# Contactless.net
KiCad netlist of a schematic drawn in EAGLE
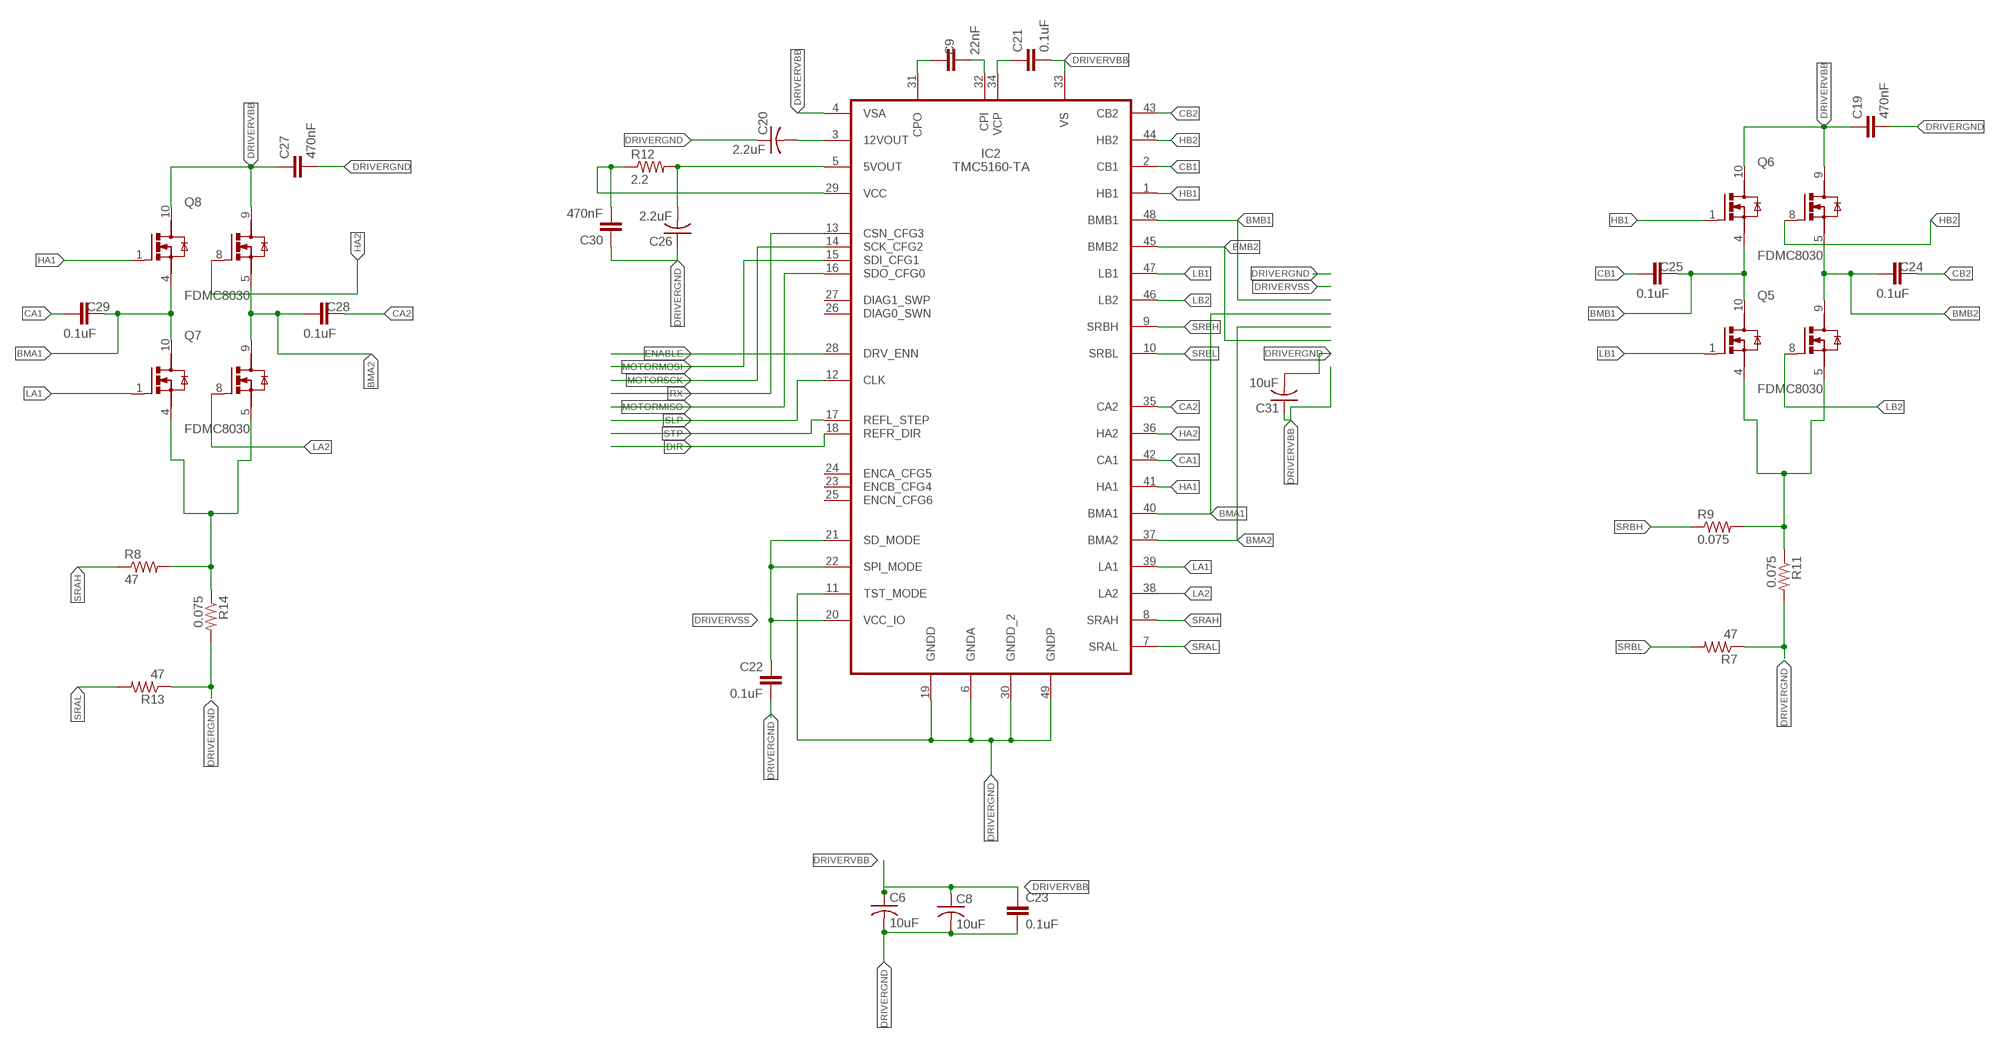
[diagram p0: schematic, sheet 1]

(export (version "E")
  (design (tool "Eeschema 10.0.6"))
  (components
    (comp (ref "C6")
      (value "10uF")
      (footprint "eagle-import:C0805")
      (libsource (lib "eagle-import") (part "C-USC0805"))
    )
    (comp (ref "C8")
      (value "10uF")
      (footprint "eagle-import:C0805")
      (libsource (lib "eagle-import") (part "C-USC0805"))
    )
    (comp (ref "C9")
      (value "22nF")
      (footprint "eagle-import:0603")
      (libsource (lib "eagle-import") (part "22NF/22,000PF-0603-50V-10%"))
    )
    (comp (ref "C19")
      (value "470nF")
      (footprint "eagle-import:0402")
      (libsource (lib "eagle-import") (part "470NF-0402-16V-10%"))
    )
    (comp (ref "C20")
      (value "2.2uF")
      (footprint "eagle-import:C0402")
      (libsource (lib "eagle-import") (part "C-USC0402"))
    )
    (comp (ref "C21")
      (value "0.1uF")
      (footprint "eagle-import:0402")
      (libsource (lib "eagle-import") (part "0.1UF-0402-16V-10%"))
    )
    (comp (ref "C22")
      (value "0.1uF")
      (footprint "eagle-import:0402")
      (libsource (lib "eagle-import") (part "0.1UF-0402-16V-10%"))
    )
    (comp (ref "C23")
      (value "0.1uF")
      (footprint "eagle-import:0402")
      (libsource (lib "eagle-import") (part "0.1UF-0402-16V-10%"))
    )
    (comp (ref "C24")
      (value "0.1uF")
      (footprint "eagle-import:0402")
      (libsource (lib "eagle-import") (part "0.1UF-0402-16V-10%"))
    )
    (comp (ref "C25")
      (value "0.1uF")
      (footprint "eagle-import:0402")
      (libsource (lib "eagle-import") (part "0.1UF-0402-16V-10%"))
    )
    (comp (ref "C26")
      (value "2.2uF")
      (footprint "eagle-import:C0402")
      (libsource (lib "eagle-import") (part "C-USC0402"))
    )
    (comp (ref "C27")
      (value "470nF")
      (footprint "eagle-import:0402")
      (libsource (lib "eagle-import") (part "470NF-0402-16V-10%"))
    )
    (comp (ref "C28")
      (value "0.1uF")
      (footprint "eagle-import:0402")
      (libsource (lib "eagle-import") (part "0.1UF-0402-16V-10%"))
    )
    (comp (ref "C29")
      (value "0.1uF")
      (footprint "eagle-import:0402")
      (libsource (lib "eagle-import") (part "0.1UF-0402-16V-10%"))
    )
    (comp (ref "C30")
      (value "470nF")
      (footprint "eagle-import:0402")
      (libsource (lib "eagle-import") (part "470NF-0402-16V-10%"))
    )
    (comp (ref "C31")
      (value "10uF")
      (footprint "eagle-import:C0805")
      (libsource (lib "eagle-import") (part "C-USC0805"))
    )
    (comp (ref "IC2")
      (value "TMC5160-TA")
      (footprint "eagle-import:TQFP48-EP")
      (fields (field (name "MF") "Trinamic Motion"))
      (libsource (lib "eagle-import") (part "TMC5160-TA"))
    )
    (comp (ref "Q5")
      (value "FDMC8030")
      (footprint "eagle-import:TRANS_FDMC8030")
      (fields (field (name "MF") "ON Semiconductor"))
      (libsource (lib "eagle-import") (part "FDMC8030"))
    )
    (comp (ref "Q6")
      (value "FDMC8030")
      (footprint "eagle-import:TRANS_FDMC8030")
      (fields (field (name "MF") "ON Semiconductor"))
      (libsource (lib "eagle-import") (part "FDMC8030"))
    )
    (comp (ref "Q7")
      (value "FDMC8030")
      (footprint "eagle-import:TRANS_FDMC8030")
      (fields (field (name "MF") "ON Semiconductor"))
      (libsource (lib "eagle-import") (part "FDMC8030"))
    )
    (comp (ref "Q8")
      (value "FDMC8030")
      (footprint "eagle-import:TRANS_FDMC8030")
      (fields (field (name "MF") "ON Semiconductor"))
      (libsource (lib "eagle-import") (part "FDMC8030"))
    )
    (comp (ref "R7")
      (value "47")
      (footprint "eagle-import:R0402")
      (libsource (lib "eagle-import") (part "R-US_R0402"))
    )
    (comp (ref "R8")
      (value "47")
      (footprint "eagle-import:R0402")
      (libsource (lib "eagle-import") (part "R-US_R0402"))
    )
    (comp (ref "R9")
      (value "0.075")
      (footprint "eagle-import:R1206")
      (libsource (lib "eagle-import") (part "R-US_R1206"))
    )
    (comp (ref "R11")
      (value "0.075")
      (footprint "eagle-import:R1206")
      (libsource (lib "eagle-import") (part "R-US_R1206"))
    )
    (comp (ref "R12")
      (value "2.2")
      (footprint "eagle-import:R0402")
      (libsource (lib "eagle-import") (part "R-US_R0402"))
    )
    (comp (ref "R13")
      (value "47")
      (footprint "eagle-import:R0402")
      (libsource (lib "eagle-import") (part "R-US_R0402"))
    )
    (comp (ref "R14")
      (value "0.075")
      (footprint "eagle-import:R1206")
      (libsource (lib "eagle-import") (part "R-US_R1206"))
    )
  )
  (nets
    (net (code "1") (name "BMA1") (class "Default")
      (node (ref "C29") (pin "2") (pinfunction "2_2") (pintype "passive"))
      (node (ref "IC2") (pin "40") (pinfunction "BMA1_40") (pintype "input"))
      (node (ref "Q7") (pin "10") (pinfunction "D1_10") (pintype "passive"))
      (node (ref "Q8") (pin "4") (pinfunction "S1_4") (pintype "passive"))
    )
    (net (code "2") (name "BMA2") (class "Default")
      (node (ref "C28") (pin "1") (pinfunction "1_1") (pintype "passive"))
      (node (ref "IC2") (pin "37") (pinfunction "BMA2_37") (pintype "input"))
      (node (ref "Q7") (pin "9") (pinfunction "D2_9") (pintype "passive"))
      (node (ref "Q8") (pin "5") (pinfunction "S2_5") (pintype "passive"))
    )
    (net (code "3") (name "BMB1") (class "Default")
      (node (ref "C25") (pin "2") (pinfunction "2_2") (pintype "passive"))
      (node (ref "IC2") (pin "48") (pinfunction "BMB1_48") (pintype "input"))
      (node (ref "Q5") (pin "10") (pinfunction "D1_10") (pintype "passive"))
      (node (ref "Q6") (pin "4") (pinfunction "S1_4") (pintype "passive"))
    )
    (net (code "4") (name "BMB2") (class "Default")
      (node (ref "C24") (pin "1") (pinfunction "1_1") (pintype "passive"))
      (node (ref "IC2") (pin "45") (pinfunction "BMB2_45") (pintype "input"))
      (node (ref "Q5") (pin "9") (pinfunction "D2_9") (pintype "passive"))
      (node (ref "Q6") (pin "5") (pinfunction "S2_5") (pintype "passive"))
    )
    (net (code "5") (name "CA1") (class "Default")
      (node (ref "C29") (pin "1") (pinfunction "1_1") (pintype "passive"))
      (node (ref "IC2") (pin "42") (pinfunction "CA1_42") (pintype "input"))
    )
    (net (code "6") (name "CA2") (class "Default")
      (node (ref "C28") (pin "2") (pinfunction "2_2") (pintype "passive"))
      (node (ref "IC2") (pin "35") (pinfunction "CA2_35") (pintype "input"))
    )
    (net (code "7") (name "CB1") (class "Default")
      (node (ref "C25") (pin "1") (pinfunction "1_1") (pintype "passive"))
      (node (ref "IC2") (pin "2") (pinfunction "CB1_2") (pintype "input"))
    )
    (net (code "8") (name "CB2") (class "Default")
      (node (ref "C24") (pin "2") (pinfunction "2_2") (pintype "passive"))
      (node (ref "IC2") (pin "43") (pinfunction "CB2_43") (pintype "input"))
    )
    (net (code "9") (name "DIR") (class "Default")
      (node (ref "IC2") (pin "18") (pinfunction "REFR_DIR_18") (pintype "input"))
    )
    (net (code "10") (name "DRIVERGND") (class "Default")
      (node (ref "C19") (pin "2") (pinfunction "2_2") (pintype "passive"))
      (node (ref "C20") (pin "1") (pinfunction "1_1") (pintype "passive"))
      (node (ref "C22") (pin "2") (pinfunction "2_2") (pintype "passive"))
      (node (ref "C23") (pin "2") (pinfunction "2_2") (pintype "passive"))
      (node (ref "C26") (pin "1") (pinfunction "1_1") (pintype "passive"))
      (node (ref "C27") (pin "2") (pinfunction "2_2") (pintype "passive"))
      (node (ref "C30") (pin "1") (pinfunction "1_1") (pintype "passive"))
      (node (ref "C31") (pin "2") (pinfunction "2_2") (pintype "passive"))
      (node (ref "C6") (pin "2") (pinfunction "2_2") (pintype "passive"))
      (node (ref "C8") (pin "2") (pinfunction "2_2") (pintype "passive"))
      (node (ref "IC2") (pin "11") (pinfunction "TST_MODE_11") (pintype "input"))
      (node (ref "IC2") (pin "19") (pinfunction "GNDD_19") (pintype "power_in"))
      (node (ref "IC2") (pin "30") (pinfunction "GNDD_2_30") (pintype "power_in"))
      (node (ref "IC2") (pin "49") (pinfunction "GNDP_49") (pintype "power_in"))
      (node (ref "IC2") (pin "6") (pinfunction "GNDA_6") (pintype "power_in"))
      (node (ref "R11") (pin "2") (pinfunction "2_2") (pintype "passive"))
      (node (ref "R13") (pin "1") (pinfunction "1_1") (pintype "passive"))
      (node (ref "R14") (pin "2") (pinfunction "2_2") (pintype "passive"))
      (node (ref "R7") (pin "1") (pinfunction "1_1") (pintype "passive"))
    )
    (net (code "11") (name "DRIVERVBB") (class "Default")
      (node (ref "C19") (pin "1") (pinfunction "1_1") (pintype "passive"))
      (node (ref "C21") (pin "2") (pinfunction "2_2") (pintype "passive"))
      (node (ref "C23") (pin "1") (pinfunction "1_1") (pintype "passive"))
      (node (ref "C27") (pin "1") (pinfunction "1_1") (pintype "passive"))
      (node (ref "C31") (pin "1") (pinfunction "1_1") (pintype "passive"))
      (node (ref "C6") (pin "1") (pinfunction "1_1") (pintype "passive"))
      (node (ref "C8") (pin "1") (pinfunction "1_1") (pintype "passive"))
      (node (ref "IC2") (pin "33") (pinfunction "VS_33") (pintype "power_in"))
      (node (ref "IC2") (pin "4") (pinfunction "VSA_4") (pintype "power_in"))
      (node (ref "Q6") (pin "10") (pinfunction "D1_10") (pintype "passive"))
      (node (ref "Q6") (pin "9") (pinfunction "D2_9") (pintype "passive"))
      (node (ref "Q8") (pin "10") (pinfunction "D1_10") (pintype "passive"))
      (node (ref "Q8") (pin "9") (pinfunction "D2_9") (pintype "passive"))
    )
    (net (code "12") (name "DRIVERVSS") (class "Default")
      (node (ref "C22") (pin "1") (pinfunction "1_1") (pintype "passive"))
      (node (ref "IC2") (pin "20") (pinfunction "VCC_IO_20") (pintype "power_in"))
      (node (ref "IC2") (pin "21") (pinfunction "SD_MODE_21") (pintype "input"))
      (node (ref "IC2") (pin "22") (pinfunction "SPI_MODE_22") (pintype "input"))
    )
    (net (code "13") (name "ENABLE") (class "Default")
      (node (ref "IC2") (pin "28") (pinfunction "DRV_ENN_28") (pintype "input"))
    )
    (net (code "14") (name "HA1") (class "Default")
      (node (ref "IC2") (pin "41") (pinfunction "HA1_41") (pintype "output"))
      (node (ref "Q8") (pin "1") (pinfunction "G1_1") (pintype "passive"))
    )
    (net (code "15") (name "HA2") (class "Default")
      (node (ref "IC2") (pin "36") (pinfunction "HA2_36") (pintype "output"))
      (node (ref "Q8") (pin "8") (pinfunction "G2_8") (pintype "passive"))
    )
    (net (code "16") (name "HB1") (class "Default")
      (node (ref "IC2") (pin "1") (pinfunction "HB1_1") (pintype "output"))
      (node (ref "Q6") (pin "1") (pinfunction "G1_1") (pintype "passive"))
    )
    (net (code "17") (name "HB2") (class "Default")
      (node (ref "IC2") (pin "44") (pinfunction "HB2_44") (pintype "output"))
      (node (ref "Q6") (pin "8") (pinfunction "G2_8") (pintype "passive"))
    )
    (net (code "18") (name "LA1") (class "Default")
      (node (ref "IC2") (pin "39") (pinfunction "LA1_39") (pintype "output"))
      (node (ref "Q7") (pin "1") (pinfunction "G1_1") (pintype "passive"))
    )
    (net (code "19") (name "LA2") (class "Default")
      (node (ref "IC2") (pin "38") (pinfunction "LA2_38") (pintype "output"))
      (node (ref "Q7") (pin "8") (pinfunction "G2_8") (pintype "passive"))
    )
    (net (code "20") (name "LB1") (class "Default")
      (node (ref "IC2") (pin "47") (pinfunction "LB1_47") (pintype "output"))
      (node (ref "Q5") (pin "1") (pinfunction "G1_1") (pintype "passive"))
    )
    (net (code "21") (name "LB2") (class "Default")
      (node (ref "IC2") (pin "46") (pinfunction "LB2_46") (pintype "output"))
      (node (ref "Q5") (pin "8") (pinfunction "G2_8") (pintype "passive"))
    )
    (net (code "22") (name "MOTORMISO") (class "Default")
      (node (ref "IC2") (pin "16") (pinfunction "SDO_CFG0_16") (pintype "output"))
    )
    (net (code "23") (name "MOTORMOSI") (class "Default")
      (node (ref "IC2") (pin "15") (pinfunction "SDI_CFG1_15") (pintype "input"))
    )
    (net (code "24") (name "MOTORSCK") (class "Default")
      (node (ref "IC2") (pin "14") (pinfunction "SCK_CFG2_14") (pintype "input"))
    )
    (net (code "25") (name "Net-(IC2-5VOUT)") (class "Default")
      (node (ref "C26") (pin "2") (pinfunction "2_2") (pintype "passive"))
      (node (ref "IC2") (pin "5") (pinfunction "5VOUT_5") (pintype "bidirectional"))
      (node (ref "R12") (pin "2") (pinfunction "2_2") (pintype "passive"))
    )
    (net (code "26") (name "Net-(IC2-12VOUT)") (class "Default")
      (node (ref "C20") (pin "2") (pinfunction "2_2") (pintype "passive"))
      (node (ref "IC2") (pin "3") (pinfunction "12VOUT_3") (pintype "bidirectional"))
    )
    (net (code "27") (name "Net-(IC2-CPI)") (class "Default")
      (node (ref "C9") (pin "2") (pinfunction "2_2") (pintype "passive"))
      (node (ref "IC2") (pin "32") (pinfunction "CPI_32") (pintype "input"))
    )
    (net (code "28") (name "Net-(IC2-CPO)") (class "Default")
      (node (ref "C9") (pin "1") (pinfunction "1_1") (pintype "passive"))
      (node (ref "IC2") (pin "31") (pinfunction "CPO_31") (pintype "input"))
    )
    (net (code "29") (name "Net-(IC2-VCC)") (class "Default")
      (node (ref "C30") (pin "2") (pinfunction "2_2") (pintype "passive"))
      (node (ref "IC2") (pin "29") (pinfunction "VCC_29") (pintype "power_in"))
      (node (ref "R12") (pin "1") (pinfunction "1_1") (pintype "passive"))
    )
    (net (code "30") (name "Net-(IC2-VCP)") (class "Default")
      (node (ref "C21") (pin "1") (pinfunction "1_1") (pintype "passive"))
      (node (ref "IC2") (pin "34") (pinfunction "VCP_34") (pintype "input"))
    )
    (net (code "31") (name "Net-(Q5-S1)") (class "Default")
      (node (ref "Q5") (pin "4") (pinfunction "S1_4") (pintype "passive"))
      (node (ref "Q5") (pin "5") (pinfunction "S2_5") (pintype "passive"))
      (node (ref "R11") (pin "1") (pinfunction "1_1") (pintype "passive"))
      (node (ref "R9") (pin "2") (pinfunction "2_2") (pintype "passive"))
    )
    (net (code "32") (name "Net-(Q7-S1)") (class "Default")
      (node (ref "Q7") (pin "4") (pinfunction "S1_4") (pintype "passive"))
      (node (ref "Q7") (pin "5") (pinfunction "S2_5") (pintype "passive"))
      (node (ref "R14") (pin "1") (pinfunction "1_1") (pintype "passive"))
      (node (ref "R8") (pin "2") (pinfunction "2_2") (pintype "passive"))
    )
    (net (code "33") (name "RX") (class "Default")
      (node (ref "IC2") (pin "13") (pinfunction "CSN_CFG3_13") (pintype "input"))
    )
    (net (code "34") (name "SLP") (class "Default")
      (node (ref "IC2") (pin "12") (pinfunction "CLK_12") (pintype "input"))
    )
    (net (code "35") (name "SRAH") (class "Default")
      (node (ref "IC2") (pin "8") (pinfunction "SRAH_8") (pintype "input"))
      (node (ref "R8") (pin "1") (pinfunction "1_1") (pintype "passive"))
    )
    (net (code "36") (name "SRAL") (class "Default")
      (node (ref "IC2") (pin "7") (pinfunction "SRAL_7") (pintype "input"))
      (node (ref "R13") (pin "2") (pinfunction "2_2") (pintype "passive"))
    )
    (net (code "37") (name "SRBH") (class "Default")
      (node (ref "IC2") (pin "9") (pinfunction "SRBH_9") (pintype "input"))
      (node (ref "R9") (pin "1") (pinfunction "1_1") (pintype "passive"))
    )
    (net (code "38") (name "SRBL") (class "Default")
      (node (ref "IC2") (pin "10") (pinfunction "SRBL_10") (pintype "input"))
      (node (ref "R7") (pin "2") (pinfunction "2_2") (pintype "passive"))
    )
    (net (code "39") (name "STP") (class "Default")
      (node (ref "IC2") (pin "17") (pinfunction "REFL_STEP_17") (pintype "input"))
    )
    (net (code "40") (name "unconnected-(IC2-DIAG0_SWN-Pad26)") (class "Default")
      (node (ref "IC2") (pin "26") (pinfunction "DIAG0_SWN_26") (pintype "bidirectional"))
    )
    (net (code "41") (name "unconnected-(IC2-DIAG1_SWP-Pad27)") (class "Default")
      (node (ref "IC2") (pin "27") (pinfunction "DIAG1_SWP_27") (pintype "bidirectional"))
    )
    (net (code "42") (name "unconnected-(IC2-ENCA_CFG5-Pad24)") (class "Default")
      (node (ref "IC2") (pin "24") (pinfunction "ENCA_CFG5_24") (pintype "input"))
    )
    (net (code "43") (name "unconnected-(IC2-ENCB_CFG4-Pad23)") (class "Default")
      (node (ref "IC2") (pin "23") (pinfunction "ENCB_CFG4_23") (pintype "input"))
    )
    (net (code "44") (name "unconnected-(IC2-ENCN_CFG6-Pad25)") (class "Default")
      (node (ref "IC2") (pin "25") (pinfunction "ENCN_CFG6_25") (pintype "input"))
    )
  )
)
